# mainBoard.net
KiCad netlist of a schematic drawn in EAGLE
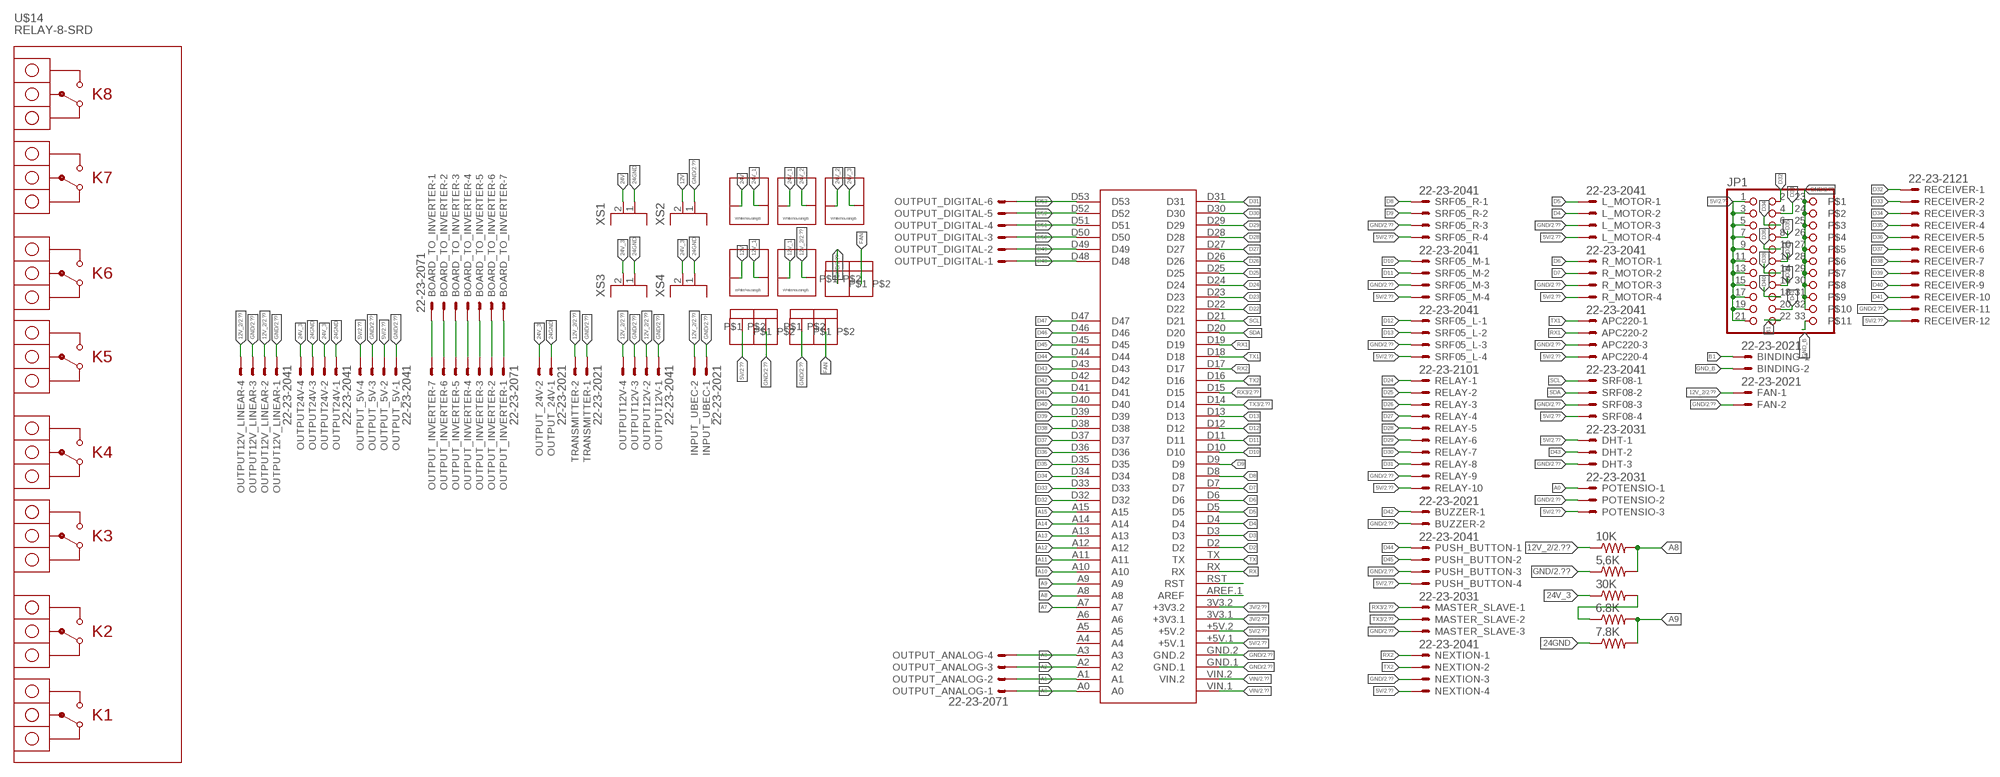
[diagram p0: schematic, sheet 1]
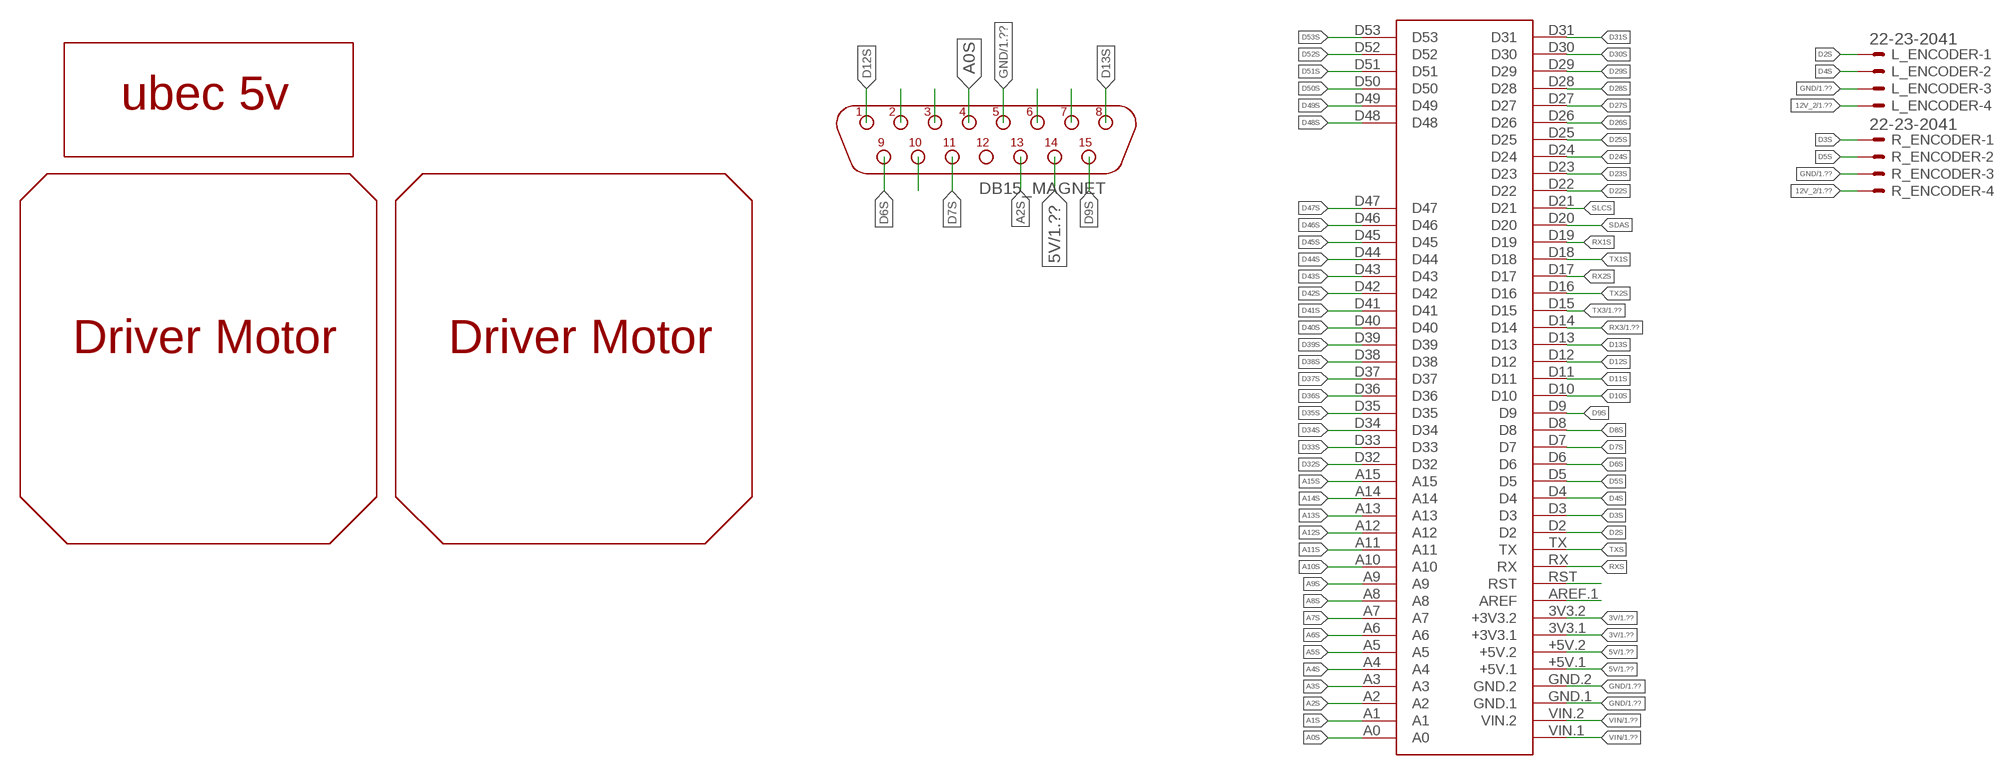
[diagram p1: schematic, sheet 2]

(export (version "E")
  (design (tool "Eeschema 10.0.6"))
  (components
    (comp (ref "5,6K")
      (value "R-US_0207/7")
      (footprint "eagle-import:0207_7")
      (libsource (lib "eagle-import") (part "R-US_0207/7"))
    )
    (comp (ref "6.8K")
      (value "R-US_0207/7")
      (footprint "eagle-import:0207_7")
      (libsource (lib "eagle-import") (part "R-US_0207/7"))
    )
    (comp (ref "7.8K")
      (value "R-US_0207/7")
      (footprint "eagle-import:0207_7")
      (libsource (lib "eagle-import") (part "R-US_0207/7"))
    )
    (comp (ref "10K")
      (value "R-US_0207/7")
      (footprint "eagle-import:0207_7")
      (libsource (lib "eagle-import") (part "R-US_0207/7"))
    )
    (comp (ref "30K")
      (value "R-US_0207/7")
      (footprint "eagle-import:0207_7")
      (libsource (lib "eagle-import") (part "R-US_0207/7"))
    )
    (comp (ref "APC220")
      (value "22-23-2041")
      (footprint "eagle-import:22-23-2041")
      (fields (field (name "MF") "MOLEX"))
      (libsource (lib "eagle-import") (part "22-23-2041"))
    )
    (comp (ref "BINDING")
      (value "22-23-2021")
      (footprint "eagle-import:22-23-2021")
      (fields (field (name "MF") "MOLEX"))
      (libsource (lib "eagle-import") (part "22-23-2021"))
    )
    (comp (ref "BOARD_TO_INVERTER")
      (value "22-23-2071")
      (footprint "eagle-import:22-23-2071")
      (fields (field (name "MF") "MOLEX"))
      (libsource (lib "eagle-import") (part "22-23-2071"))
    )
    (comp (ref "BUZZER")
      (value "22-23-2021")
      (footprint "eagle-import:22-23-2021")
      (fields (field (name "MF") "MOLEX"))
      (libsource (lib "eagle-import") (part "22-23-2021"))
    )
    (comp (ref "DHT")
      (value "22-23-2031")
      (footprint "eagle-import:22-23-2031")
      (fields (field (name "MF") "MOLEX"))
      (libsource (lib "eagle-import") (part "22-23-2031"))
    )
    (comp (ref "EMERGENCY")
      (value "WHB")
      (footprint "eagle-import:WHB")
      (libsource (lib "eagle-import") (part "WHB"))
    )
    (comp (ref "FAN")
      (value "22-23-2021")
      (footprint "eagle-import:22-23-2021")
      (fields (field (name "MF") "MOLEX"))
      (libsource (lib "eagle-import") (part "22-23-2021"))
    )
    (comp (ref "FANLEFT")
      (value "TERMINALBLOCK5MM")
      (footprint "eagle-import:TERMINALBLOCK5MM")
      (libsource (lib "eagle-import") (part "TERMINALBLOCK5MM"))
    )
    (comp (ref "FANRIGHT")
      (value "TERMINALBLOCK5MM")
      (footprint "eagle-import:TERMINALBLOCK5MM")
      (libsource (lib "eagle-import") (part "TERMINALBLOCK5MM"))
    )
    (comp (ref "FUSE12V")
      (value "WHB")
      (footprint "eagle-import:WHB")
      (libsource (lib "eagle-import") (part "WHB"))
    )
    (comp (ref "FUSE24V")
      (value "WHB")
      (footprint "eagle-import:WHB")
      (libsource (lib "eagle-import") (part "WHB"))
    )
    (comp (ref "INPUT_UBEC")
      (value "22-23-2021")
      (footprint "eagle-import:22-23-2021")
      (fields (field (name "MF") "MOLEX"))
      (libsource (lib "eagle-import") (part "22-23-2021"))
    )
    (comp (ref "JP1")
      (value "PINHD-2X11")
      (footprint "eagle-import:2X11")
      (libsource (lib "eagle-import") (part "PINHD-2X11"))
    )
    (comp (ref "L_MOTOR")
      (value "22-23-2041")
      (footprint "eagle-import:22-23-2041")
      (fields (field (name "MF") "MOLEX"))
      (libsource (lib "eagle-import") (part "22-23-2041"))
    )
    (comp (ref "MASTER_SLAVE")
      (value "22-23-2031")
      (footprint "eagle-import:22-23-2031")
      (fields (field (name "MF") "MOLEX"))
      (libsource (lib "eagle-import") (part "22-23-2031"))
    )
    (comp (ref "NEXTION")
      (value "22-23-2041")
      (footprint "eagle-import:22-23-2041")
      (fields (field (name "MF") "MOLEX"))
      (libsource (lib "eagle-import") (part "22-23-2041"))
    )
    (comp (ref "OUTPUT12V")
      (value "22-23-2041")
      (footprint "eagle-import:22-23-2041")
      (fields (field (name "MF") "MOLEX"))
      (libsource (lib "eagle-import") (part "22-23-2041"))
    )
    (comp (ref "OUTPUT12V_LINEAR")
      (value "22-23-2041")
      (footprint "eagle-import:22-23-2041")
      (fields (field (name "MF") "MOLEX"))
      (libsource (lib "eagle-import") (part "22-23-2041"))
    )
    (comp (ref "OUTPUT24V")
      (value "22-23-2041")
      (footprint "eagle-import:22-23-2041")
      (fields (field (name "MF") "MOLEX"))
      (libsource (lib "eagle-import") (part "22-23-2041"))
    )
    (comp (ref "OUTPUT_5V")
      (value "22-23-2041")
      (footprint "eagle-import:22-23-2041")
      (fields (field (name "MF") "MOLEX"))
      (libsource (lib "eagle-import") (part "22-23-2041"))
    )
    (comp (ref "OUTPUT_24V")
      (value "22-23-2021")
      (footprint "eagle-import:22-23-2021")
      (fields (field (name "MF") "MOLEX"))
      (libsource (lib "eagle-import") (part "22-23-2021"))
    )
    (comp (ref "OUTPUT_ANALOG")
      (value "22-23-2071")
      (footprint "eagle-import:22-23-2071")
      (fields (field (name "MF") "MOLEX"))
      (libsource (lib "eagle-import") (part "22-23-2071"))
    )
    (comp (ref "OUTPUT_DIGITAL")
      (value "22-23-2061")
      (footprint "eagle-import:22-23-2061")
      (fields (field (name "MF") "MOLEX"))
      (libsource (lib "eagle-import") (part "22-23-2061"))
    )
    (comp (ref "OUTPUT_INVERTER")
      (value "22-23-2071")
      (footprint "eagle-import:22-23-2071")
      (fields (field (name "MF") "MOLEX"))
      (libsource (lib "eagle-import") (part "22-23-2071"))
    )
    (comp (ref "POTENSIO")
      (value "22-23-2031")
      (footprint "eagle-import:22-23-2031")
      (fields (field (name "MF") "MOLEX"))
      (libsource (lib "eagle-import") (part "22-23-2031"))
    )
    (comp (ref "PUSH_BUTTON")
      (value "22-23-2041")
      (footprint "eagle-import:22-23-2041")
      (fields (field (name "MF") "MOLEX"))
      (libsource (lib "eagle-import") (part "22-23-2041"))
    )
    (comp (ref "RECEIVER")
      (value "22-23-2121")
      (footprint "eagle-import:22-23-2121")
      (fields (field (name "MF") "MOLEX"))
      (libsource (lib "eagle-import") (part "22-23-2121"))
    )
    (comp (ref "RELAY")
      (value "22-23-2101")
      (footprint "eagle-import:22-23-2101")
      (fields (field (name "MF") "MOLEX"))
      (libsource (lib "eagle-import") (part "22-23-2101"))
    )
    (comp (ref "R_MOTOR")
      (value "22-23-2041")
      (footprint "eagle-import:22-23-2041")
      (fields (field (name "MF") "MOLEX"))
      (libsource (lib "eagle-import") (part "22-23-2041"))
    )
    (comp (ref "SRF05_L")
      (value "22-23-2041")
      (footprint "eagle-import:22-23-2041")
      (fields (field (name "MF") "MOLEX"))
      (libsource (lib "eagle-import") (part "22-23-2041"))
    )
    (comp (ref "SRF05_M")
      (value "22-23-2041")
      (footprint "eagle-import:22-23-2041")
      (fields (field (name "MF") "MOLEX"))
      (libsource (lib "eagle-import") (part "22-23-2041"))
    )
    (comp (ref "SRF05_R")
      (value "22-23-2041")
      (footprint "eagle-import:22-23-2041")
      (fields (field (name "MF") "MOLEX"))
      (libsource (lib "eagle-import") (part "22-23-2041"))
    )
    (comp (ref "SRF08")
      (value "22-23-2041")
      (footprint "eagle-import:22-23-2041")
      (fields (field (name "MF") "MOLEX"))
      (libsource (lib "eagle-import") (part "22-23-2041"))
    )
    (comp (ref "SWITCH24V")
      (value "WHB")
      (footprint "eagle-import:WHB")
      (libsource (lib "eagle-import") (part "WHB"))
    )
    (comp (ref "SWTICH12V")
      (value "WHB")
      (footprint "eagle-import:WHB")
      (libsource (lib "eagle-import") (part "WHB"))
    )
    (comp (ref "TRANSMITTER")
      (value "22-23-2021")
      (footprint "eagle-import:22-23-2021")
      (fields (field (name "MF") "MOLEX"))
      (libsource (lib "eagle-import") (part "22-23-2021"))
    )
    (comp (ref "U$1")
      (value "MEGA2560_MIKRO")
      (footprint "eagle-import:MEGA2560_MIKRO")
      (libsource (lib "eagle-import") (part "MEGA2560_MIKRO"))
    )
    (comp (ref "U$14")
      (value "RELAY-8-SRD")
      (footprint "eagle-import:RELAY-8-SRD")
      (libsource (lib "eagle-import") (part "RELAY-8-SRD"))
    )
    (comp (ref "UBEC_OUTPUT")
      (value "TERMINALBLOCK5MM")
      (footprint "eagle-import:TERMINALBLOCK5MM")
      (libsource (lib "eagle-import") (part "TERMINALBLOCK5MM"))
    )
    (comp (ref "XS1")
      (value "2P")
      (footprint "eagle-import:DG55CB-2P-1")
      (libsource (lib "eagle-import") (part "2P"))
    )
    (comp (ref "XS2")
      (value "2P")
      (footprint "eagle-import:DG55CB-2P-1")
      (libsource (lib "eagle-import") (part "2P"))
    )
    (comp (ref "XS3")
      (value "2P")
      (footprint "eagle-import:DG55CB-2P-1")
      (libsource (lib "eagle-import") (part "2P"))
    )
    (comp (ref "XS4")
      (value "2P")
      (footprint "eagle-import:DG55CB-2P-1")
      (libsource (lib "eagle-import") (part "2P"))
    )
    (comp (ref "DB15_MAGNET")
      (value "DB15M/90")
      (footprint "eagle-import:D-15M_90")
      (libsource (lib "eagle-import") (part "DB15M/90"))
    )
    (comp (ref "L_ENCODER")
      (value "22-23-2041")
      (footprint "eagle-import:22-23-2041")
      (fields (field (name "MF") "MOLEX"))
      (libsource (lib "eagle-import") (part "22-23-2041"))
    )
    (comp (ref "R_ENCODER")
      (value "22-23-2041")
      (footprint "eagle-import:22-23-2041")
      (fields (field (name "MF") "MOLEX"))
      (libsource (lib "eagle-import") (part "22-23-2041"))
    )
    (comp (ref "U$2")
      (value "MEGA2560_MIKRO")
      (footprint "eagle-import:MEGA2560_MIKRO")
      (libsource (lib "eagle-import") (part "MEGA2560_MIKRO"))
    )
    (comp (ref "U$11")
      (value "BT2")
      (footprint "eagle-import:IBT2")
      (libsource (lib "eagle-import") (part "BT2"))
    )
    (comp (ref "U$12")
      (value "BT2")
      (footprint "eagle-import:IBT2")
      (libsource (lib "eagle-import") (part "BT2"))
    )
    (comp (ref "U$13")
      (value "UBEC")
      (footprint "eagle-import:AD")
      (libsource (lib "eagle-import") (part "UBEC"))
    )
  )
  (nets
    (net (code "1") (name "3V") (class "Default")
      (node (ref "U$1") (pin "3V3.1") (pinfunction "+3V3.1_3V3.1") (pintype "bidirectional"))
      (node (ref "U$1") (pin "3V3.2") (pinfunction "+3V3.2_3V3.2") (pintype "bidirectional"))
      (node (ref "U$2") (pin "3V3.1") (pinfunction "+3V3.1_3V3.1") (pintype "bidirectional"))
      (node (ref "U$2") (pin "3V3.2") (pinfunction "+3V3.2_3V3.2") (pintype "bidirectional"))
    )
    (net (code "2") (name "5V") (class "Default")
      (node (ref "APC220") (pin "4") (pinfunction "S_4") (pintype "passive"))
      (node (ref "DB15_MAGNET") (pin "14") (pinfunction "14_14") (pintype "passive"))
      (node (ref "DHT") (pin "1") (pinfunction "S_1") (pintype "passive"))
      (node (ref "JP1") (pin "1") (pinfunction "1_1") (pintype "passive"))
      (node (ref "JP1") (pin "11") (pinfunction "11_11") (pintype "passive"))
      (node (ref "JP1") (pin "13") (pinfunction "13_13") (pintype "passive"))
      (node (ref "JP1") (pin "15") (pinfunction "15_15") (pintype "passive"))
      (node (ref "JP1") (pin "17") (pinfunction "17_17") (pintype "passive"))
      (node (ref "JP1") (pin "19") (pinfunction "19_19") (pintype "passive"))
      (node (ref "JP1") (pin "21") (pinfunction "21_21") (pintype "passive"))
      (node (ref "JP1") (pin "3") (pinfunction "3_3") (pintype "passive"))
      (node (ref "JP1") (pin "5") (pinfunction "5_5") (pintype "passive"))
      (node (ref "JP1") (pin "7") (pinfunction "7_7") (pintype "passive"))
      (node (ref "JP1") (pin "9") (pinfunction "9_9") (pintype "passive"))
      (node (ref "L_MOTOR") (pin "4") (pinfunction "S_4") (pintype "passive"))
      (node (ref "NEXTION") (pin "4") (pinfunction "S_4") (pintype "passive"))
      (node (ref "OUTPUT_5V") (pin "2") (pinfunction "S_2") (pintype "passive"))
      (node (ref "OUTPUT_5V") (pin "4") (pinfunction "S_4") (pintype "passive"))
      (node (ref "POTENSIO") (pin "3") (pinfunction "S_3") (pintype "passive"))
      (node (ref "PUSH_BUTTON") (pin "4") (pinfunction "S_4") (pintype "passive"))
      (node (ref "RECEIVER") (pin "12") (pinfunction "S_12") (pintype "passive"))
      (node (ref "RELAY") (pin "10") (pinfunction "S_10") (pintype "passive"))
      (node (ref "R_MOTOR") (pin "4") (pinfunction "S_4") (pintype "passive"))
      (node (ref "SRF05_L") (pin "4") (pinfunction "S_4") (pintype "passive"))
      (node (ref "SRF05_M") (pin "4") (pinfunction "S_4") (pintype "passive"))
      (node (ref "SRF05_R") (pin "4") (pinfunction "S_4") (pintype "passive"))
      (node (ref "SRF08") (pin "4") (pinfunction "S_4") (pintype "passive"))
      (node (ref "U$1") (pin "+5V.1") (pinfunction "+5V.1_+5V.1") (pintype "bidirectional"))
      (node (ref "U$1") (pin "+5V.2") (pinfunction "+5V.2_+5V.2") (pintype "bidirectional"))
      (node (ref "U$2") (pin "+5V.1") (pinfunction "+5V.1_+5V.1") (pintype "bidirectional"))
      (node (ref "U$2") (pin "+5V.2") (pinfunction "+5V.2_+5V.2") (pintype "bidirectional"))
      (node (ref "UBEC_OUTPUT") (pin "P$1") (pinfunction "P$1_P$1") (pintype "bidirectional"))
    )
    (net (code "3") (name "12V") (class "Default")
      (node (ref "FUSE12V") (pin "P$1") (pinfunction "P$1_P$1") (pintype "bidirectional"))
      (node (ref "XS2") (pin "2") (pinfunction "P$2_2") (pintype "bidirectional"))
    )
    (net (code "4") (name "12V_1") (class "Default")
      (node (ref "FUSE12V") (pin "P$2") (pinfunction "P$2_P$2") (pintype "bidirectional"))
      (node (ref "SWTICH12V") (pin "P$1") (pinfunction "P$1_P$1") (pintype "bidirectional"))
    )
    (net (code "5") (name "12V_2") (class "Default")
      (node (ref "10K") (pin "1") (pinfunction "1_1") (pintype "passive"))
      (node (ref "FAN") (pin "1") (pinfunction "S_1") (pintype "passive"))
      (node (ref "INPUT_UBEC") (pin "2") (pinfunction "S_2") (pintype "passive"))
      (node (ref "L_ENCODER") (pin "4") (pinfunction "S_4") (pintype "passive"))
      (node (ref "OUTPUT12V") (pin "2") (pinfunction "S_2") (pintype "passive"))
      (node (ref "OUTPUT12V") (pin "4") (pinfunction "S_4") (pintype "passive"))
      (node (ref "OUTPUT12V_LINEAR") (pin "2") (pinfunction "S_2") (pintype "passive"))
      (node (ref "OUTPUT12V_LINEAR") (pin "4") (pinfunction "S_4") (pintype "passive"))
      (node (ref "R_ENCODER") (pin "4") (pinfunction "S_4") (pintype "passive"))
      (node (ref "SWTICH12V") (pin "P$2") (pinfunction "P$2_P$2") (pintype "bidirectional"))
      (node (ref "TRANSMITTER") (pin "2") (pinfunction "S_2") (pintype "passive"))
    )
    (net (code "6") (name "24GND") (class "Default")
      (node (ref "7.8K") (pin "1") (pinfunction "1_1") (pintype "passive"))
      (node (ref "OUTPUT24V") (pin "1") (pinfunction "S_1") (pintype "passive"))
      (node (ref "OUTPUT24V") (pin "3") (pinfunction "S_3") (pintype "passive"))
      (node (ref "OUTPUT_24V") (pin "1") (pinfunction "S_1") (pintype "passive"))
      (node (ref "XS1") (pin "1") (pinfunction "P$1_1") (pintype "bidirectional"))
      (node (ref "XS3") (pin "1") (pinfunction "P$1_1") (pintype "bidirectional"))
      (node (ref "XS4") (pin "1") (pinfunction "P$1_1") (pintype "bidirectional"))
    )
    (net (code "7") (name "24V") (class "Default")
      (node (ref "FUSE24V") (pin "P$1") (pinfunction "P$1_P$1") (pintype "bidirectional"))
      (node (ref "XS1") (pin "2") (pinfunction "P$2_2") (pintype "bidirectional"))
    )
    (net (code "8") (name "24V_1") (class "Default")
      (node (ref "FUSE24V") (pin "P$2") (pinfunction "P$2_P$2") (pintype "bidirectional"))
      (node (ref "SWITCH24V") (pin "P$1") (pinfunction "P$1_P$1") (pintype "bidirectional"))
    )
    (net (code "9") (name "24V_2") (class "Default")
      (node (ref "EMERGENCY") (pin "P$1") (pinfunction "P$1_P$1") (pintype "bidirectional"))
      (node (ref "SWITCH24V") (pin "P$2") (pinfunction "P$2_P$2") (pintype "bidirectional"))
    )
    (net (code "10") (name "24V_3") (class "Default")
      (node (ref "30K") (pin "1") (pinfunction "1_1") (pintype "passive"))
      (node (ref "EMERGENCY") (pin "P$2") (pinfunction "P$2_P$2") (pintype "bidirectional"))
      (node (ref "OUTPUT24V") (pin "2") (pinfunction "S_2") (pintype "passive"))
      (node (ref "OUTPUT24V") (pin "4") (pinfunction "S_4") (pintype "passive"))
      (node (ref "OUTPUT_24V") (pin "2") (pinfunction "S_2") (pintype "passive"))
      (node (ref "XS3") (pin "2") (pinfunction "P$2_2") (pintype "bidirectional"))
      (node (ref "XS4") (pin "2") (pinfunction "P$2_2") (pintype "bidirectional"))
    )
    (net (code "11") (name "A0") (class "Default")
      (node (ref "OUTPUT_ANALOG") (pin "1") (pinfunction "S_1") (pintype "passive"))
      (node (ref "POTENSIO") (pin "1") (pinfunction "S_1") (pintype "passive"))
      (node (ref "U$1") (pin "A0") (pinfunction "A0_A0") (pintype "bidirectional"))
    )
    (net (code "12") (name "A0S") (class "Default")
      (node (ref "DB15_MAGNET") (pin "4") (pinfunction "4_4") (pintype "passive"))
      (node (ref "U$2") (pin "A0") (pinfunction "A0_A0") (pintype "bidirectional"))
    )
    (net (code "13") (name "A1") (class "Default")
      (node (ref "OUTPUT_ANALOG") (pin "2") (pinfunction "S_2") (pintype "passive"))
      (node (ref "U$1") (pin "A1") (pinfunction "A1_A1") (pintype "bidirectional"))
    )
    (net (code "14") (name "A1S") (class "Default")
      (node (ref "U$2") (pin "A1") (pinfunction "A1_A1") (pintype "bidirectional"))
    )
    (net (code "15") (name "A2") (class "Default")
      (node (ref "OUTPUT_ANALOG") (pin "3") (pinfunction "S_3") (pintype "passive"))
      (node (ref "U$1") (pin "A2") (pinfunction "A2_A2") (pintype "bidirectional"))
    )
    (net (code "16") (name "A2S") (class "Default")
      (node (ref "DB15_MAGNET") (pin "13") (pinfunction "13_13") (pintype "passive"))
      (node (ref "U$2") (pin "A2") (pinfunction "A2_A2") (pintype "bidirectional"))
    )
    (net (code "17") (name "A3") (class "Default")
      (node (ref "OUTPUT_ANALOG") (pin "4") (pinfunction "S_4") (pintype "passive"))
      (node (ref "U$1") (pin "A3") (pinfunction "A3_A3") (pintype "bidirectional"))
    )
    (net (code "18") (name "A3S") (class "Default")
      (node (ref "U$2") (pin "A3") (pinfunction "A3_A3") (pintype "bidirectional"))
    )
    (net (code "19") (name "A4S") (class "Default")
      (node (ref "U$2") (pin "A4") (pinfunction "A4_A4") (pintype "bidirectional"))
    )
    (net (code "20") (name "A5S") (class "Default")
      (node (ref "U$2") (pin "A5") (pinfunction "A5_A5") (pintype "bidirectional"))
    )
    (net (code "21") (name "A6S") (class "Default")
      (node (ref "U$2") (pin "A6") (pinfunction "A6_A6") (pintype "bidirectional"))
    )
    (net (code "22") (name "A7") (class "Default")
      (node (ref "U$1") (pin "A7") (pinfunction "A7_A7") (pintype "bidirectional"))
    )
    (net (code "23") (name "A7S") (class "Default")
      (node (ref "U$2") (pin "A7") (pinfunction "A7_A7") (pintype "bidirectional"))
    )
    (net (code "24") (name "A8") (class "Default")
      (node (ref "10K") (pin "2") (pinfunction "2_2") (pintype "passive"))
      (node (ref "5,6K") (pin "2") (pinfunction "2_2") (pintype "passive"))
      (node (ref "U$1") (pin "A8") (pinfunction "A8_A8") (pintype "bidirectional"))
    )
    (net (code "25") (name "A8S") (class "Default")
      (node (ref "U$2") (pin "A8") (pinfunction "A8_A8") (pintype "bidirectional"))
    )
    (net (code "26") (name "A9") (class "Default")
      (node (ref "6.8K") (pin "2") (pinfunction "2_2") (pintype "passive"))
      (node (ref "7.8K") (pin "2") (pinfunction "2_2") (pintype "passive"))
      (node (ref "U$1") (pin "A9") (pinfunction "A9_A9") (pintype "bidirectional"))
    )
    (net (code "27") (name "A9S") (class "Default")
      (node (ref "U$2") (pin "A9") (pinfunction "A9_A9") (pintype "bidirectional"))
    )
    (net (code "28") (name "A10") (class "Default")
      (node (ref "U$1") (pin "A10") (pinfunction "A10_A10") (pintype "bidirectional"))
    )
    (net (code "29") (name "A10S") (class "Default")
      (node (ref "U$2") (pin "A10") (pinfunction "A10_A10") (pintype "bidirectional"))
    )
    (net (code "30") (name "A11") (class "Default")
      (node (ref "U$1") (pin "A11") (pinfunction "A11_A11") (pintype "bidirectional"))
    )
    (net (code "31") (name "A11S") (class "Default")
      (node (ref "U$2") (pin "A11") (pinfunction "A11_A11") (pintype "bidirectional"))
    )
    (net (code "32") (name "A12") (class "Default")
      (node (ref "U$1") (pin "A12") (pinfunction "A12_A12") (pintype "bidirectional"))
    )
    (net (code "33") (name "A12S") (class "Default")
      (node (ref "U$2") (pin "A12") (pinfunction "A12_A12") (pintype "bidirectional"))
    )
    (net (code "34") (name "A13") (class "Default")
      (node (ref "U$1") (pin "A13") (pinfunction "A13_A13") (pintype "bidirectional"))
    )
    (net (code "35") (name "A13S") (class "Default")
      (node (ref "U$2") (pin "A13") (pinfunction "A13_A13") (pintype "bidirectional"))
    )
    (net (code "36") (name "A14") (class "Default")
      (node (ref "U$1") (pin "A14") (pinfunction "A14_A14") (pintype "bidirectional"))
    )
    (net (code "37") (name "A14S") (class "Default")
      (node (ref "U$2") (pin "A14") (pinfunction "A14_A14") (pintype "bidirectional"))
    )
    (net (code "38") (name "A15") (class "Default")
      (node (ref "U$1") (pin "A15") (pinfunction "A15_A15") (pintype "bidirectional"))
    )
    (net (code "39") (name "A15S") (class "Default")
      (node (ref "U$2") (pin "A15") (pinfunction "A15_A15") (pintype "bidirectional"))
    )
    (net (code "40") (name "B1") (class "Default")
      (node (ref "BINDING") (pin "1") (pinfunction "S_1") (pintype "passive"))
      (node (ref "JP1") (pin "22") (pinfunction "22_22") (pintype "passive"))
    )
    (net (code "41") (name "D2") (class "Default")
      (node (ref "U$1") (pin "D2") (pinfunction "D2_D2") (pintype "bidirectional"))
    )
    (net (code "42") (name "D2S") (class "Default")
      (node (ref "L_ENCODER") (pin "1") (pinfunction "S_1") (pintype "passive"))
      (node (ref "U$2") (pin "D2") (pinfunction "D2_D2") (pintype "bidirectional"))
    )
    (net (code "43") (name "D3") (class "Default")
      (node (ref "U$1") (pin "D3") (pinfunction "D3_D3") (pintype "bidirectional"))
    )
    (net (code "44") (name "D3S") (class "Default")
      (node (ref "R_ENCODER") (pin "1") (pinfunction "S_1") (pintype "passive"))
      (node (ref "U$2") (pin "D3") (pinfunction "D3_D3") (pintype "bidirectional"))
    )
    (net (code "45") (name "D4") (class "Default")
      (node (ref "L_MOTOR") (pin "2") (pinfunction "S_2") (pintype "passive"))
      (node (ref "U$1") (pin "D4") (pinfunction "D4_D4") (pintype "bidirectional"))
    )
    (net (code "46") (name "D4S") (class "Default")
      (node (ref "L_ENCODER") (pin "2") (pinfunction "S_2") (pintype "passive"))
      (node (ref "U$2") (pin "D4") (pinfunction "D4_D4") (pintype "bidirectional"))
    )
    (net (code "47") (name "D5") (class "Default")
      (node (ref "L_MOTOR") (pin "1") (pinfunction "S_1") (pintype "passive"))
      (node (ref "U$1") (pin "D5") (pinfunction "D5_D5") (pintype "bidirectional"))
    )
    (net (code "48") (name "D5S") (class "Default")
      (node (ref "R_ENCODER") (pin "2") (pinfunction "S_2") (pintype "passive"))
      (node (ref "U$2") (pin "D5") (pinfunction "D5_D5") (pintype "bidirectional"))
    )
    (net (code "49") (name "D6") (class "Default")
      (node (ref "R_MOTOR") (pin "1") (pinfunction "S_1") (pintype "passive"))
      (node (ref "U$1") (pin "D6") (pinfunction "D6_D6") (pintype "bidirectional"))
    )
    (net (code "50") (name "D6S") (class "Default")
      (node (ref "DB15_MAGNET") (pin "9") (pinfunction "9_9") (pintype "passive"))
      (node (ref "U$2") (pin "D6") (pinfunction "D6_D6") (pintype "bidirectional"))
    )
    (net (code "51") (name "D7") (class "Default")
      (node (ref "R_MOTOR") (pin "2") (pinfunction "S_2") (pintype "passive"))
      (node (ref "U$1") (pin "D7") (pinfunction "D7_D7") (pintype "bidirectional"))
    )
    (net (code "52") (name "D7S") (class "Default")
      (node (ref "DB15_MAGNET") (pin "11") (pinfunction "11_11") (pintype "passive"))
      (node (ref "U$2") (pin "D7") (pinfunction "D7_D7") (pintype "bidirectional"))
    )
    (net (code "53") (name "D8") (class "Default")
      (node (ref "SRF05_R") (pin "1") (pinfunction "S_1") (pintype "passive"))
      (node (ref "U$1") (pin "D8") (pinfunction "D8_D8") (pintype "bidirectional"))
    )
    (net (code "54") (name "D8S") (class "Default")
      (node (ref "U$2") (pin "D8") (pinfunction "D8_D8") (pintype "bidirectional"))
    )
    (net (code "55") (name "D9") (class "Default")
      (node (ref "SRF05_R") (pin "2") (pinfunction "S_2") (pintype "passive"))
      (node (ref "U$1") (pin "D9") (pinfunction "D9_D9") (pintype "bidirectional"))
    )
    (net (code "56") (name "D9S") (class "Default")
      (node (ref "DB15_MAGNET") (pin "15") (pinfunction "15_15") (pintype "passive"))
      (node (ref "U$2") (pin "D9") (pinfunction "D9_D9") (pintype "bidirectional"))
    )
    (net (code "57") (name "D10") (class "Default")
      (node (ref "SRF05_M") (pin "1") (pinfunction "S_1") (pintype "passive"))
      (node (ref "U$1") (pin "D10") (pinfunction "D10_D10") (pintype "bidirectional"))
    )
    (net (code "58") (name "D10S") (class "Default")
      (node (ref "U$2") (pin "D10") (pinfunction "D10_D10") (pintype "bidirectional"))
    )
    (net (code "59") (name "D11") (class "Default")
      (node (ref "SRF05_M") (pin "2") (pinfunction "S_2") (pintype "passive"))
      (node (ref "U$1") (pin "D11") (pinfunction "D11_D11") (pintype "bidirectional"))
    )
    (net (code "60") (name "D11S") (class "Default")
      (node (ref "U$2") (pin "D11") (pinfunction "D11_D11") (pintype "bidirectional"))
    )
    (net (code "61") (name "D12") (class "Default")
      (node (ref "SRF05_L") (pin "1") (pinfunction "S_1") (pintype "passive"))
      (node (ref "U$1") (pin "D12") (pinfunction "D12_D12") (pintype "bidirectional"))
    )
    (net (code "62") (name "D12S") (class "Default")
      (node (ref "DB15_MAGNET") (pin "1") (pinfunction "1_1") (pintype "passive"))
      (node (ref "U$2") (pin "D12") (pinfunction "D12_D12") (pintype "bidirectional"))
    )
    (net (code "63") (name "D13") (class "Default")
      (node (ref "SRF05_L") (pin "2") (pinfunction "S_2") (pintype "passive"))
      (node (ref "U$1") (pin "D13") (pinfunction "D13_D13") (pintype "bidirectional"))
    )
    (net (code "64") (name "D13S") (class "Default")
      (node (ref "DB15_MAGNET") (pin "8") (pinfunction "8_8") (pintype "passive"))
      (node (ref "U$2") (pin "D13") (pinfunction "D13_D13") (pintype "bidirectional"))
    )
    (net (code "65") (name "D22") (class "Default")
      (node (ref "U$1") (pin "D22") (pinfunction "D22_D22") (pintype "bidirectional"))
    )
    (net (code "66") (name "D22S") (class "Default")
      (node (ref "U$2") (pin "D22") (pinfunction "D22_D22") (pintype "bidirectional"))
    )
    (net (code "67") (name "D23") (class "Default")
      (node (ref "U$1") (pin "D23") (pinfunction "D23_D23") (pintype "bidirectional"))
    )
    (net (code "68") (name "D23S") (class "Default")
      (node (ref "U$2") (pin "D23") (pinfunction "D23_D23") (pintype "bidirectional"))
    )
    (net (code "69") (name "D24") (class "Default")
      (node (ref "RELAY") (pin "1") (pinfunction "S_1") (pintype "passive"))
      (node (ref "U$1") (pin "D24") (pinfunction "D24_D24") (pintype "bidirectional"))
    )
    (net (code "70") (name "D24S") (class "Default")
      (node (ref "U$2") (pin "D24") (pinfunction "D24_D24") (pintype "bidirectional"))
    )
    (net (code "71") (name "D25") (class "Default")
      (node (ref "RELAY") (pin "2") (pinfunction "S_2") (pintype "passive"))
      (node (ref "U$1") (pin "D25") (pinfunction "D25_D25") (pintype "bidirectional"))
    )
    (net (code "72") (name "D25S") (class "Default")
      (node (ref "U$2") (pin "D25") (pinfunction "D25_D25") (pintype "bidirectional"))
    )
    (net (code "73") (name "D26") (class "Default")
      (node (ref "RELAY") (pin "3") (pinfunction "S_3") (pintype "passive"))
      (node (ref "U$1") (pin "D26") (pinfunction "D26_D26") (pintype "bidirectional"))
    )
    (net (code "74") (name "D26S") (class "Default")
      (node (ref "U$2") (pin "D26") (pinfunction "D26_D26") (pintype "bidirectional"))
    )
    (net (code "75") (name "D27") (class "Default")
      (node (ref "RELAY") (pin "4") (pinfunction "S_4") (pintype "passive"))
      (node (ref "U$1") (pin "D27") (pinfunction "D27_D27") (pintype "bidirectional"))
    )
    (net (code "76") (name "D27S") (class "Default")
      (node (ref "U$2") (pin "D27") (pinfunction "D27_D27") (pintype "bidirectional"))
    )
    (net (code "77") (name "D28") (class "Default")
      (node (ref "RELAY") (pin "5") (pinfunction "S_5") (pintype "passive"))
      (node (ref "U$1") (pin "D28") (pinfunction "D28_D28") (pintype "bidirectional"))
    )
    (net (code "78") (name "D28S") (class "Default")
      (node (ref "U$2") (pin "D28") (pinfunction "D28_D28") (pintype "bidirectional"))
    )
    (net (code "79") (name "D29") (class "Default")
      (node (ref "RELAY") (pin "6") (pinfunction "S_6") (pintype "passive"))
      (node (ref "U$1") (pin "D29") (pinfunction "D29_D29") (pintype "bidirectional"))
    )
    (net (code "80") (name "D29S") (class "Default")
      (node (ref "U$2") (pin "D29") (pinfunction "D29_D29") (pintype "bidirectional"))
    )
    (net (code "81") (name "D30") (class "Default")
      (node (ref "RELAY") (pin "7") (pinfunction "S_7") (pintype "passive"))
      (node (ref "U$1") (pin "D30") (pinfunction "D30_D30") (pintype "bidirectional"))
    )
    (net (code "82") (name "D30S") (class "Default")
      (node (ref "U$2") (pin "D30") (pinfunction "D30_D30") (pintype "bidirectional"))
    )
    (net (code "83") (name "D31") (class "Default")
      (node (ref "RELAY") (pin "8") (pinfunction "S_8") (pintype "passive"))
      (node (ref "U$1") (pin "D31") (pinfunction "D31_D31") (pintype "bidirectional"))
    )
    (net (code "84") (name "D31S") (class "Default")
      (node (ref "U$2") (pin "D31") (pinfunction "D31_D31") (pintype "bidirectional"))
    )
    (net (code "85") (name "D32") (class "Default")
      (node (ref "JP1") (pin "2") (pinfunction "2_2") (pintype "passive"))
      (node (ref "RECEIVER") (pin "1") (pinfunction "S_1") (pintype "passive"))
      (node (ref "U$1") (pin "D32") (pinfunction "D32_D32") (pintype "bidirectional"))
    )
    (net (code "86") (name "D32S") (class "Default")
      (node (ref "U$2") (pin "D32") (pinfunction "D32_D32") (pintype "bidirectional"))
    )
    (net (code "87") (name "D33") (class "Default")
      (node (ref "JP1") (pin "4") (pinfunction "4_4") (pintype "passive"))
      (node (ref "RECEIVER") (pin "2") (pinfunction "S_2") (pintype "passive"))
      (node (ref "U$1") (pin "D33") (pinfunction "D33_D33") (pintype "bidirectional"))
    )
    (net (code "88") (name "D33S") (class "Default")
      (node (ref "U$2") (pin "D33") (pinfunction "D33_D33") (pintype "bidirectional"))
    )
    (net (code "89") (name "D34") (class "Default")
      (node (ref "JP1") (pin "6") (pinfunction "6_6") (pintype "passive"))
      (node (ref "RECEIVER") (pin "3") (pinfunction "S_3") (pintype "passive"))
      (node (ref "U$1") (pin "D34") (pinfunction "D34_D34") (pintype "bidirectional"))
    )
    (net (code "90") (name "D34S") (class "Default")
      (node (ref "U$2") (pin "D34") (pinfunction "D34_D34") (pintype "bidirectional"))
    )
    (net (code "91") (name "D35") (class "Default")
      (node (ref "JP1") (pin "8") (pinfunction "8_8") (pintype "passive"))
      (node (ref "RECEIVER") (pin "4") (pinfunction "S_4") (pintype "passive"))
      (node (ref "U$1") (pin "D35") (pinfunction "D35_D35") (pintype "bidirectional"))
    )
    (net (code "92") (name "D35S") (class "Default")
      (node (ref "U$2") (pin "D35") (pinfunction "D35_D35") (pintype "bidirectional"))
    )
    (net (code "93") (name "D36") (class "Default")
      (node (ref "JP1") (pin "10") (pinfunction "10_10") (pintype "passive"))
      (node (ref "RECEIVER") (pin "5") (pinfunction "S_5") (pintype "passive"))
      (node (ref "U$1") (pin "D36") (pinfunction "D36_D36") (pintype "bidirectional"))
    )
    (net (code "94") (name "D36S") (class "Default")
      (node (ref "U$2") (pin "D36") (pinfunction "D36_D36") (pintype "bidirectional"))
    )
    (net (code "95") (name "D37") (class "Default")
      (node (ref "JP1") (pin "12") (pinfunction "12_12") (pintype "passive"))
      (node (ref "RECEIVER") (pin "6") (pinfunction "S_6") (pintype "passive"))
      (node (ref "U$1") (pin "D37") (pinfunction "D37_D37") (pintype "bidirectional"))
    )
    (net (code "96") (name "D37S") (class "Default")
      (node (ref "U$2") (pin "D37") (pinfunction "D37_D37") (pintype "bidirectional"))
    )
    (net (code "97") (name "D38") (class "Default")
      (node (ref "JP1") (pin "14") (pinfunction "14_14") (pintype "passive"))
      (node (ref "RECEIVER") (pin "7") (pinfunction "S_7") (pintype "passive"))
      (node (ref "U$1") (pin "D38") (pinfunction "D38_D38") (pintype "bidirectional"))
    )
    (net (code "98") (name "D38S") (class "Default")
      (node (ref "U$2") (pin "D38") (pinfunction "D38_D38") (pintype "bidirectional"))
    )
    (net (code "99") (name "D39") (class "Default")
      (node (ref "JP1") (pin "16") (pinfunction "16_16") (pintype "passive"))
      (node (ref "RECEIVER") (pin "8") (pinfunction "S_8") (pintype "passive"))
      (node (ref "U$1") (pin "D39") (pinfunction "D39_D39") (pintype "bidirectional"))
    )
    (net (code "100") (name "D39S") (class "Default")
      (node (ref "U$2") (pin "D39") (pinfunction "D39_D39") (pintype "bidirectional"))
    )
    (net (code "101") (name "D40") (class "Default")
      (node (ref "JP1") (pin "18") (pinfunction "18_18") (pintype "passive"))
      (node (ref "RECEIVER") (pin "9") (pinfunction "S_9") (pintype "passive"))
      (node (ref "U$1") (pin "D40") (pinfunction "D40_D40") (pintype "bidirectional"))
    )
    (net (code "102") (name "D40S") (class "Default")
      (node (ref "U$2") (pin "D40") (pinfunction "D40_D40") (pintype "bidirectional"))
    )
    (net (code "103") (name "D41") (class "Default")
      (node (ref "JP1") (pin "20") (pinfunction "20_20") (pintype "passive"))
      (node (ref "RECEIVER") (pin "10") (pinfunction "S_10") (pintype "passive"))
      (node (ref "U$1") (pin "D41") (pinfunction "D41_D41") (pintype "bidirectional"))
    )
    (net (code "104") (name "D41S") (class "Default")
      (node (ref "U$2") (pin "D41") (pinfunction "D41_D41") (pintype "bidirectional"))
    )
    (net (code "105") (name "D42") (class "Default")
      (node (ref "BUZZER") (pin "1") (pinfunction "S_1") (pintype "passive"))
      (node (ref "U$1") (pin "D42") (pinfunction "D42_D42") (pintype "bidirectional"))
    )
    (net (code "106") (name "D42S") (class "Default")
      (node (ref "U$2") (pin "D42") (pinfunction "D42_D42") (pintype "bidirectional"))
    )
    (net (code "107") (name "D43") (class "Default")
      (node (ref "DHT") (pin "2") (pinfunction "S_2") (pintype "passive"))
      (node (ref "U$1") (pin "D43") (pinfunction "D43_D43") (pintype "bidirectional"))
    )
    (net (code "108") (name "D43S") (class "Default")
      (node (ref "U$2") (pin "D43") (pinfunction "D43_D43") (pintype "bidirectional"))
    )
    (net (code "109") (name "D44") (class "Default")
      (node (ref "PUSH_BUTTON") (pin "1") (pinfunction "S_1") (pintype "passive"))
      (node (ref "U$1") (pin "D44") (pinfunction "D44_D44") (pintype "bidirectional"))
    )
    (net (code "110") (name "D44S") (class "Default")
      (node (ref "U$2") (pin "D44") (pinfunction "D44_D44") (pintype "bidirectional"))
    )
    (net (code "111") (name "D45") (class "Default")
      (node (ref "PUSH_BUTTON") (pin "2") (pinfunction "S_2") (pintype "passive"))
      (node (ref "U$1") (pin "D45") (pinfunction "D45_D45") (pintype "bidirectional"))
    )
    (net (code "112") (name "D45S") (class "Default")
      (node (ref "U$2") (pin "D45") (pinfunction "D45_D45") (pintype "bidirectional"))
    )
    (net (code "113") (name "D46") (class "Default")
      (node (ref "U$1") (pin "D46") (pinfunction "D46_D46") (pintype "bidirectional"))
    )
    (net (code "114") (name "D46S") (class "Default")
      (node (ref "U$2") (pin "D46") (pinfunction "D46_D46") (pintype "bidirectional"))
    )
    (net (code "115") (name "D47") (class "Default")
      (node (ref "U$1") (pin "D47") (pinfunction "D47_D47") (pintype "bidirectional"))
    )
    (net (code "116") (name "D47S") (class "Default")
      (node (ref "U$2") (pin "D47") (pinfunction "D47_D47") (pintype "bidirectional"))
    )
    (net (code "117") (name "D48") (class "Default")
      (node (ref "OUTPUT_DIGITAL") (pin "1") (pinfunction "S_1") (pintype "passive"))
      (node (ref "U$1") (pin "D48") (pinfunction "D48_D48") (pintype "bidirectional"))
    )
    (net (code "118") (name "D48S") (class "Default")
      (node (ref "U$2") (pin "D48") (pinfunction "D48_D48") (pintype "bidirectional"))
    )
    (net (code "119") (name "D49") (class "Default")
      (node (ref "OUTPUT_DIGITAL") (pin "2") (pinfunction "S_2") (pintype "passive"))
      (node (ref "U$1") (pin "D49") (pinfunction "D49_D49") (pintype "bidirectional"))
    )
    (net (code "120") (name "D49S") (class "Default")
      (node (ref "U$2") (pin "D49") (pinfunction "D49_D49") (pintype "bidirectional"))
    )
    (net (code "121") (name "D50") (class "Default")
      (node (ref "OUTPUT_DIGITAL") (pin "3") (pinfunction "S_3") (pintype "passive"))
      (node (ref "U$1") (pin "D50") (pinfunction "D50_D50") (pintype "bidirectional"))
    )
    (net (code "122") (name "D50S") (class "Default")
      (node (ref "U$2") (pin "D50") (pinfunction "D50_D50") (pintype "bidirectional"))
    )
    (net (code "123") (name "D51") (class "Default")
      (node (ref "OUTPUT_DIGITAL") (pin "4") (pinfunction "S_4") (pintype "passive"))
      (node (ref "U$1") (pin "D51") (pinfunction "D51_D51") (pintype "bidirectional"))
    )
    (net (code "124") (name "D51S") (class "Default")
      (node (ref "U$2") (pin "D51") (pinfunction "D51_D51") (pintype "bidirectional"))
    )
    (net (code "125") (name "D52") (class "Default")
      (node (ref "OUTPUT_DIGITAL") (pin "5") (pinfunction "S_5") (pintype "passive"))
      (node (ref "U$1") (pin "D52") (pinfunction "D52_D52") (pintype "bidirectional"))
    )
    (net (code "126") (name "D52S") (class "Default")
      (node (ref "U$2") (pin "D52") (pinfunction "D52_D52") (pintype "bidirectional"))
    )
    (net (code "127") (name "D53") (class "Default")
      (node (ref "OUTPUT_DIGITAL") (pin "6") (pinfunction "S_6") (pintype "passive"))
      (node (ref "U$1") (pin "D53") (pinfunction "D53_D53") (pintype "bidirectional"))
    )
    (net (code "128") (name "D53S") (class "Default")
      (node (ref "U$2") (pin "D53") (pinfunction "D53_D53") (pintype "bidirectional"))
    )
    (net (code "129") (name "FAN") (class "Default")
      (node (ref "FANLEFT") (pin "P$2") (pinfunction "P$2_P$2") (pintype "bidirectional"))
      (node (ref "FANRIGHT") (pin "P$2") (pinfunction "P$2_P$2") (pintype "bidirectional"))
    )
    (net (code "130") (name "GND") (class "Default")
      (node (ref "5,6K") (pin "1") (pinfunction "1_1") (pintype "passive"))
      (node (ref "APC220") (pin "3") (pinfunction "S_3") (pintype "passive"))
      (node (ref "BUZZER") (pin "2") (pinfunction "S_2") (pintype "passive"))
      (node (ref "DB15_MAGNET") (pin "5") (pinfunction "5_5") (pintype "passive"))
      (node (ref "DHT") (pin "3") (pinfunction "S_3") (pintype "passive"))
      (node (ref "FAN") (pin "2") (pinfunction "S_2") (pintype "passive"))
      (node (ref "FANLEFT") (pin "P$1") (pinfunction "P$1_P$1") (pintype "bidirectional"))
      (node (ref "FANRIGHT") (pin "P$1") (pinfunction "P$1_P$1") (pintype "bidirectional"))
      (node (ref "INPUT_UBEC") (pin "1") (pinfunction "S_1") (pintype "passive"))
      (node (ref "JP1") (pin "23") (pinfunction "P$1_23") (pintype "bidirectional"))
      (node (ref "JP1") (pin "24") (pinfunction "P$2_24") (pintype "bidirectional"))
      (node (ref "JP1") (pin "25") (pinfunction "P$3_25") (pintype "bidirectional"))
      (node (ref "JP1") (pin "26") (pinfunction "P$4_26") (pintype "bidirectional"))
      (node (ref "JP1") (pin "27") (pinfunction "P$5_27") (pintype "bidirectional"))
      (node (ref "JP1") (pin "28") (pinfunction "P$6_28") (pintype "bidirectional"))
      (node (ref "JP1") (pin "29") (pinfunction "P$7_29") (pintype "bidirectional"))
      (node (ref "JP1") (pin "30") (pinfunction "P$8_30") (pintype "bidirectional"))
      (node (ref "JP1") (pin "31") (pinfunction "P$9_31") (pintype "bidirectional"))
      (node (ref "JP1") (pin "32") (pinfunction "P$10_32") (pintype "bidirectional"))
      (node (ref "L_ENCODER") (pin "3") (pinfunction "S_3") (pintype "passive"))
      (node (ref "L_MOTOR") (pin "3") (pinfunction "S_3") (pintype "passive"))
      (node (ref "MASTER_SLAVE") (pin "3") (pinfunction "S_3") (pintype "passive"))
      (node (ref "NEXTION") (pin "3") (pinfunction "S_3") (pintype "passive"))
      (node (ref "OUTPUT12V") (pin "1") (pinfunction "S_1") (pintype "passive"))
      (node (ref "OUTPUT12V") (pin "3") (pinfunction "S_3") (pintype "passive"))
      (node (ref "OUTPUT12V_LINEAR") (pin "1") (pinfunction "S_1") (pintype "passive"))
      (node (ref "OUTPUT12V_LINEAR") (pin "3") (pinfunction "S_3") (pintype "passive"))
      (node (ref "OUTPUT_5V") (pin "1") (pinfunction "S_1") (pintype "passive"))
      (node (ref "OUTPUT_5V") (pin "3") (pinfunction "S_3") (pintype "passive"))
      (node (ref "POTENSIO") (pin "2") (pinfunction "S_2") (pintype "passive"))
      (node (ref "PUSH_BUTTON") (pin "3") (pinfunction "S_3") (pintype "passive"))
      (node (ref "RECEIVER") (pin "11") (pinfunction "S_11") (pintype "passive"))
      (node (ref "RELAY") (pin "9") (pinfunction "S_9") (pintype "passive"))
      (node (ref "R_ENCODER") (pin "3") (pinfunction "S_3") (pintype "passive"))
      (node (ref "R_MOTOR") (pin "3") (pinfunction "S_3") (pintype "passive"))
      (node (ref "SRF05_L") (pin "3") (pinfunction "S_3") (pintype "passive"))
      (node (ref "SRF05_M") (pin "3") (pinfunction "S_3") (pintype "passive"))
      (node (ref "SRF05_R") (pin "3") (pinfunction "S_3") (pintype "passive"))
      (node (ref "SRF08") (pin "3") (pinfunction "S_3") (pintype "passive"))
      (node (ref "TRANSMITTER") (pin "1") (pinfunction "S_1") (pintype "passive"))
      (node (ref "U$1") (pin "GND.1") (pinfunction "GND.1_GND.1") (pintype "bidirectional"))
      (node (ref "U$1") (pin "GND.2") (pinfunction "GND.2_GND.2") (pintype "bidirectional"))
      (node (ref "U$2") (pin "GND.1") (pinfunction "GND.1_GND.1") (pintype "bidirectional"))
      (node (ref "U$2") (pin "GND.2") (pinfunction "GND.2_GND.2") (pintype "bidirectional"))
      (node (ref "UBEC_OUTPUT") (pin "P$2") (pinfunction "P$2_P$2") (pintype "bidirectional"))
      (node (ref "XS2") (pin "1") (pinfunction "P$1_1") (pintype "bidirectional"))
    )
    (net (code "131") (name "GND_B") (class "Default")
      (node (ref "BINDING") (pin "2") (pinfunction "S_2") (pintype "passive"))
      (node (ref "JP1") (pin "33") (pinfunction "P$11_33") (pintype "bidirectional"))
    )
    (net (code "132") (name "Net-(30K-Pad2)") (class "Default")
      (node (ref "30K") (pin "2") (pinfunction "2_2") (pintype "passive"))
      (node (ref "6.8K") (pin "1") (pinfunction "1_1") (pintype "passive"))
    )
    (net (code "133") (name "Net-(BOARD_TO_INVERTERA-S)") (class "Default")
      (node (ref "BOARD_TO_INVERTER") (pin "1") (pinfunction "S_1") (pintype "passive"))
      (node (ref "OUTPUT_INVERTER") (pin "7") (pinfunction "S_7") (pintype "passive"))
    )
    (net (code "134") (name "Net-(BOARD_TO_INVERTERB-S)") (class "Default")
      (node (ref "BOARD_TO_INVERTER") (pin "2") (pinfunction "S_2") (pintype "passive"))
      (node (ref "OUTPUT_INVERTER") (pin "6") (pinfunction "S_6") (pintype "passive"))
    )
    (net (code "135") (name "Net-(BOARD_TO_INVERTERC-S)") (class "Default")
      (node (ref "BOARD_TO_INVERTER") (pin "3") (pinfunction "S_3") (pintype "passive"))
      (node (ref "OUTPUT_INVERTER") (pin "5") (pinfunction "S_5") (pintype "passive"))
    )
    (net (code "136") (name "Net-(BOARD_TO_INVERTERD-S)") (class "Default")
      (node (ref "BOARD_TO_INVERTER") (pin "4") (pinfunction "S_4") (pintype "passive"))
      (node (ref "OUTPUT_INVERTER") (pin "4") (pinfunction "S_4") (pintype "passive"))
    )
    (net (code "137") (name "Net-(BOARD_TO_INVERTERE-S)") (class "Default")
      (node (ref "BOARD_TO_INVERTER") (pin "5") (pinfunction "S_5") (pintype "passive"))
      (node (ref "OUTPUT_INVERTER") (pin "3") (pinfunction "S_3") (pintype "passive"))
    )
    (net (code "138") (name "Net-(BOARD_TO_INVERTERF-S)") (class "Default")
      (node (ref "BOARD_TO_INVERTER") (pin "6") (pinfunction "S_6") (pintype "passive"))
      (node (ref "OUTPUT_INVERTER") (pin "2") (pinfunction "S_2") (pintype "passive"))
    )
    (net (code "139") (name "Net-(BOARD_TO_INVERTERG-S)") (class "Default")
      (node (ref "BOARD_TO_INVERTER") (pin "7") (pinfunction "S_7") (pintype "passive"))
      (node (ref "OUTPUT_INVERTER") (pin "1") (pinfunction "S_1") (pintype "passive"))
    )
    (net (code "140") (name "RX") (class "Default")
      (node (ref "U$1") (pin "RX") (pinfunction "RX_RX") (pintype "bidirectional"))
    )
    (net (code "141") (name "RX1") (class "Default")
      (node (ref "APC220") (pin "2") (pinfunction "S_2") (pintype "passive"))
      (node (ref "U$1") (pin "D19") (pinfunction "D19_D19") (pintype "bidirectional"))
    )
    (net (code "142") (name "RX1S") (class "Default")
      (node (ref "U$2") (pin "D19") (pinfunction "D19_D19") (pintype "bidirectional"))
    )
    (net (code "143") (name "RX2") (class "Default")
      (node (ref "NEXTION") (pin "1") (pinfunction "S_1") (pintype "passive"))
      (node (ref "U$1") (pin "D17") (pinfunction "D17_D17") (pintype "bidirectional"))
    )
    (net (code "144") (name "RX2S") (class "Default")
      (node (ref "U$2") (pin "D17") (pinfunction "D17_D17") (pintype "bidirectional"))
    )
    (net (code "145") (name "RX3") (class "Default")
      (node (ref "MASTER_SLAVE") (pin "1") (pinfunction "S_1") (pintype "passive"))
      (node (ref "U$1") (pin "D15") (pinfunction "D15_D15") (pintype "bidirectional"))
      (node (ref "U$2") (pin "D14") (pinfunction "D14_D14") (pintype "bidirectional"))
    )
    (net (code "146") (name "RXS") (class "Default")
      (node (ref "U$2") (pin "RX") (pinfunction "RX_RX") (pintype "bidirectional"))
    )
    (net (code "147") (name "SCL") (class "Default")
      (node (ref "SRF08") (pin "1") (pinfunction "S_1") (pintype "passive"))
      (node (ref "U$1") (pin "D21") (pinfunction "D21_D21") (pintype "bidirectional"))
    )
    (net (code "148") (name "SDA") (class "Default")
      (node (ref "SRF08") (pin "2") (pinfunction "S_2") (pintype "passive"))
      (node (ref "U$1") (pin "D20") (pinfunction "D20_D20") (pintype "bidirectional"))
    )
    (net (code "149") (name "SDAS") (class "Default")
      (node (ref "U$2") (pin "D20") (pinfunction "D20_D20") (pintype "bidirectional"))
    )
    (net (code "150") (name "SLCS") (class "Default")
      (node (ref "U$2") (pin "D21") (pinfunction "D21_D21") (pintype "bidirectional"))
    )
    (net (code "151") (name "TX") (class "Default")
      (node (ref "U$1") (pin "TX") (pinfunction "TX_TX") (pintype "bidirectional"))
    )
    (net (code "152") (name "TX1") (class "Default")
      (node (ref "APC220") (pin "1") (pinfunction "S_1") (pintype "passive"))
      (node (ref "U$1") (pin "D18") (pinfunction "D18_D18") (pintype "bidirectional"))
    )
    (net (code "153") (name "TX1S") (class "Default")
      (node (ref "U$2") (pin "D18") (pinfunction "D18_D18") (pintype "bidirectional"))
    )
    (net (code "154") (name "TX2") (class "Default")
      (node (ref "NEXTION") (pin "2") (pinfunction "S_2") (pintype "passive"))
      (node (ref "U$1") (pin "D16") (pinfunction "D16_D16") (pintype "bidirectional"))
    )
    (net (code "155") (name "TX2S") (class "Default")
      (node (ref "U$2") (pin "D16") (pinfunction "D16_D16") (pintype "bidirectional"))
    )
    (net (code "156") (name "TX3") (class "Default")
      (node (ref "MASTER_SLAVE") (pin "2") (pinfunction "S_2") (pintype "passive"))
      (node (ref "U$1") (pin "D14") (pinfunction "D14_D14") (pintype "bidirectional"))
      (node (ref "U$2") (pin "D15") (pinfunction "D15_D15") (pintype "bidirectional"))
    )
    (net (code "157") (name "TXS") (class "Default")
      (node (ref "U$2") (pin "TX") (pinfunction "TX_TX") (pintype "bidirectional"))
    )
    (net (code "158") (name "VIN") (class "Default")
      (node (ref "U$1") (pin "VIN.1") (pinfunction "VIN.1_VIN.1") (pintype "bidirectional"))
      (node (ref "U$1") (pin "VIN.2") (pinfunction "VIN.2_VIN.2") (pintype "bidirectional"))
      (node (ref "U$2") (pin "VIN.1") (pinfunction "VIN.1_VIN.1") (pintype "bidirectional"))
      (node (ref "U$2") (pin "VIN.2") (pinfunction "VIN.2_VIN.2") (pintype "bidirectional"))
    )
    (net (code "159") (name "unconnected-(DB15_MAGNET-Pad2)") (class "Default")
      (node (ref "DB15_MAGNET") (pin "2") (pinfunction "2_2") (pintype "passive"))
    )
    (net (code "160") (name "unconnected-(DB15_MAGNET-Pad3)") (class "Default")
      (node (ref "DB15_MAGNET") (pin "3") (pinfunction "3_3") (pintype "passive"))
    )
    (net (code "161") (name "unconnected-(DB15_MAGNET-Pad6)") (class "Default")
      (node (ref "DB15_MAGNET") (pin "6") (pinfunction "6_6") (pintype "passive"))
    )
    (net (code "162") (name "unconnected-(DB15_MAGNET-Pad7)") (class "Default")
      (node (ref "DB15_MAGNET") (pin "7") (pinfunction "7_7") (pintype "passive"))
    )
    (net (code "163") (name "unconnected-(DB15_MAGNET-Pad10)") (class "Default")
      (node (ref "DB15_MAGNET") (pin "10") (pinfunction "10_10") (pintype "passive"))
    )
    (net (code "164") (name "unconnected-(DB15_MAGNET-Pad12)") (class "Default")
      (node (ref "DB15_MAGNET") (pin "12") (pinfunction "12_12") (pintype "passive"))
    )
    (net (code "165") (name "unconnected-(U$1-AREF-PadAREF.1)") (class "Default")
      (node (ref "U$1") (pin "AREF.1") (pinfunction "AREF_AREF.1") (pintype "bidirectional"))
    )
    (net (code "166") (name "unconnected-(U$1-PadA4)") (class "Default")
      (node (ref "U$1") (pin "A4") (pinfunction "A4_A4") (pintype "bidirectional"))
    )
    (net (code "167") (name "unconnected-(U$1-PadA5)") (class "Default")
      (node (ref "U$1") (pin "A5") (pinfunction "A5_A5") (pintype "bidirectional"))
    )
    (net (code "168") (name "unconnected-(U$1-PadA6)") (class "Default")
      (node (ref "U$1") (pin "A6") (pinfunction "A6_A6") (pintype "bidirectional"))
    )
    (net (code "169") (name "unconnected-(U$1-PadRST)") (class "Default")
      (node (ref "U$1") (pin "RST") (pinfunction "RST_RST") (pintype "bidirectional"))
    )
    (net (code "170") (name "unconnected-(U$2-AREF-PadAREF.1)") (class "Default")
      (node (ref "U$2") (pin "AREF.1") (pinfunction "AREF_AREF.1") (pintype "bidirectional"))
    )
    (net (code "171") (name "unconnected-(U$2-PadRST)") (class "Default")
      (node (ref "U$2") (pin "RST") (pinfunction "RST_RST") (pintype "bidirectional"))
    )
  )
)
